# PowerSupply.net
KiCad netlist of a schematic drawn in Altium Designer
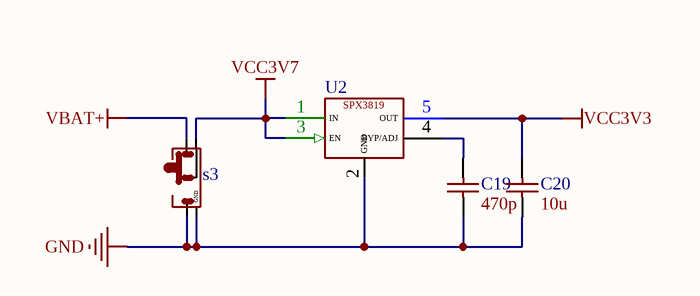
[diagram p0: PowerSupply.SchDoc]

(export (version "E")
  (design (tool "Eeschema 10.0.6"))
  (components
    (comp (ref "C19")
      (value "470p")
      (footprint "C0402_h")
      (description "Capacitor")
      (fields (field (name "PUBLISHER") "Altium Limited"))
      (libsource (lib "电子元件封装库") (part "贴片电容-无极性"))
    )
    (comp (ref "C20")
      (value "10u")
      (footprint "C0402_h")
      (description "Capacitor")
      (fields (field (name "PUBLISHER") "Altium Limited"))
      (libsource (lib "电子元件封装库") (part "贴片电容-无极性"))
    )
    (comp (ref "s3")
      (value "switch")
      (footprint "侧动贴片开关")
      (description "拨动开关")
      (libsource (lib "电子元件封装库") (part "拨动开关"))
    )
    (comp (ref "U2")
      (value "SPX3819")
      (footprint "SOT23-5")
      (description "500mA, Low-Noise LDO Voltage Regulator")
      (libsource (lib "电子元件封装库") (part "SPX3819"))
    )
  )
  (nets
    (net (code "1") (name "GND") (class "Default")
      (node (ref "C19") (pin "2") (pinfunction "2_2") (pintype "passive"))
      (node (ref "C20") (pin "2") (pinfunction "2_2") (pintype "passive"))
      (node (ref "U2") (pin "2") (pinfunction "GND_2") (pintype "passive"))
      (node (ref "s3") (pin "0") (pinfunction "GND_0") (pintype "passive"))
      (node (ref "s3") (pin "3") (pinfunction "R_3") (pintype "passive"))
    )
    (net (code "2") (name "Net-(U2-BYP{slash}ADJ)") (class "Default")
      (node (ref "C19") (pin "1") (pinfunction "1_1") (pintype "passive"))
      (node (ref "U2") (pin "4") (pinfunction "BYP/ADJ_4") (pintype "passive"))
    )
    (net (code "3") (name "VBAT+") (class "Default")
      (node (ref "s3") (pin "1") (pinfunction "L_1") (pintype "passive"))
    )
    (net (code "4") (name "VCC3V3") (class "Default")
      (node (ref "C20") (pin "1") (pinfunction "1_1") (pintype "passive"))
      (node (ref "U2") (pin "5") (pinfunction "OUT_5") (pintype "power_in"))
    )
    (net (code "5") (name "VCC3V7") (class "Default")
      (node (ref "U2") (pin "1") (pinfunction "IN_1") (pintype "power_in"))
      (node (ref "U2") (pin "3") (pinfunction "EN_3") (pintype "input"))
      (node (ref "s3") (pin "2") (pinfunction "mid_2") (pintype "passive"))
    )
  )
)
